# CRUVI.net
KiCad netlist of a schematic drawn in Altium Designer
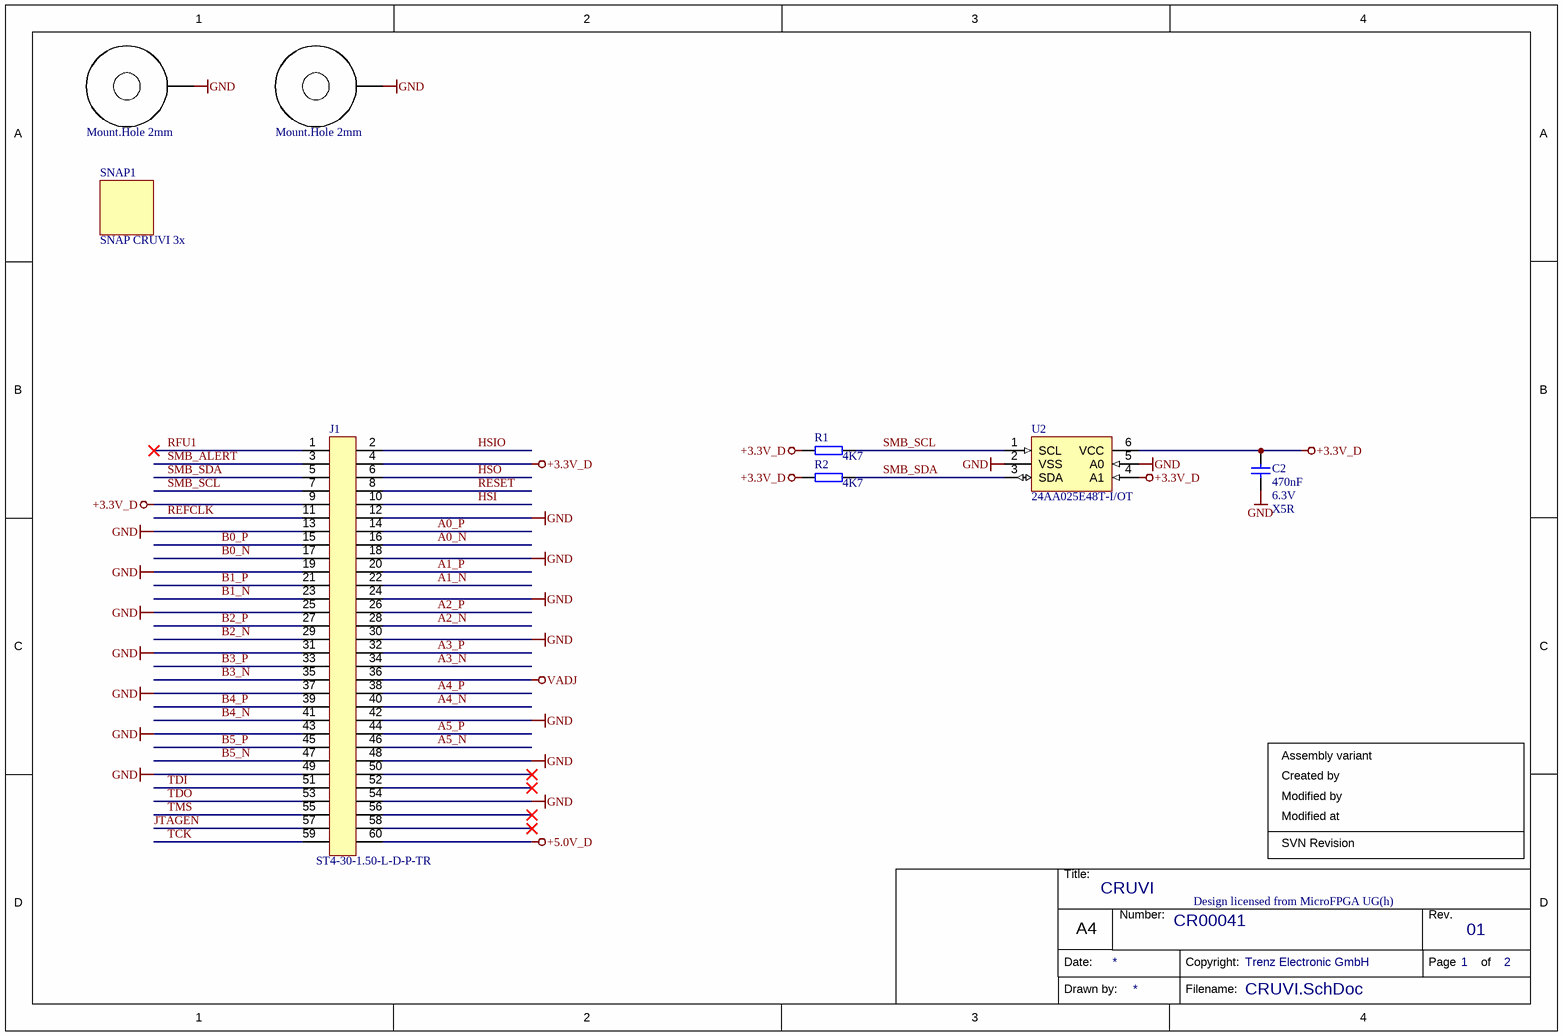
[diagram p0: CRUVI.SchDoc]

(export (version "E")
  (design (tool "Eeschema 10.0.6"))
  (components
    (comp (ref "C2")
      (value "470nF")
      (footprint "CAPC1005X55N")
      (description "KON 470nF 6,3V X5R SMD BF 1005 (0402)")
      (fields (field (name "VOLTAGE") "6.3V") (field (name "TECHNOLOGY") "X5R"))
      (libsource (lib "TE") (part "CAP-NP"))
    )
    (comp (ref "H1") (value "Mount.Hole 2mm") (footprint "MHole2_2mm") (libsource (lib "TE") (part "MHole")))
    (comp (ref "H2") (value "Mount.Hole 2mm") (footprint "MHole2_2mm") (libsource (lib "TE") (part "MHole")))
    (comp (ref "J1")
      (value "ST4-30-1.50-L-D-P-TR")
      (footprint "ST4-30-1_50-L-D")
      (libsource (lib "TE") (part "CON-60"))
    )
    (comp (ref "R1")
      (value "4K7")
      (footprint "RESC1005X40N")
      (description "WID SMD 4K7 1% 0,063W BF 1005 (0402)")
      (fields (field (name "TOLERANCE") "1%"))
      (libsource (lib "TE") (part "RES"))
    )
    (comp (ref "R2")
      (value "4K7")
      (footprint "RESC1005X40N")
      (description "WID SMD 4K7 1% 0,063W BF 1005 (0402)")
      (fields (field (name "TOLERANCE") "1%"))
      (libsource (lib "TE") (part "RES"))
    )
    (comp (ref "SNAP1")
      (value "SNAP CRUVI 3x")
      (footprint "CRUVI_3x_Snap")
      (description "SNAP for CRUVI 3x")
      (libsource (lib "TE") (part "DUMMY"))
    )
    (comp (ref "U2")
      (value "24AA025E48T-I/OT")
      (footprint "SOT95P280X145-6N")
      (libsource (lib "TE") (part "24AA025E48"))
    )
  )
  (nets
    (net (code "1") (name "+3.3V_D") (class "Default")
      (node (ref "C2") (pin "1") (pinfunction "1_1") (pintype "passive"))
      (node (ref "J1") (pin "4") (pinfunction "4_4") (pintype "passive"))
      (node (ref "J1") (pin "9") (pinfunction "9_9") (pintype "passive"))
      (node (ref "R1") (pin "1") (pinfunction "1_1") (pintype "passive"))
      (node (ref "R2") (pin "1") (pinfunction "1_1") (pintype "passive"))
      (node (ref "U2") (pin "4") (pinfunction "A1_4") (pintype "input"))
      (node (ref "U2") (pin "6") (pinfunction "VCC_6") (pintype "power_in"))
    )
    (net (code "2") (name "+5.0V_D") (class "Default")
      (node (ref "J1") (pin "60") (pinfunction "60_60") (pintype "passive"))
    )
    (net (code "3") (name "/A0_N") (class "Default")
      (node (ref "J1") (pin "16") (pinfunction "16_16") (pintype "passive"))
    )
    (net (code "4") (name "/A0_P") (class "Default")
      (node (ref "J1") (pin "14") (pinfunction "14_14") (pintype "passive"))
    )
    (net (code "5") (name "/A1_N") (class "Default")
      (node (ref "J1") (pin "22") (pinfunction "22_22") (pintype "passive"))
    )
    (net (code "6") (name "/A1_P") (class "Default")
      (node (ref "J1") (pin "20") (pinfunction "20_20") (pintype "passive"))
    )
    (net (code "7") (name "/A2_N") (class "Default")
      (node (ref "J1") (pin "28") (pinfunction "28_28") (pintype "passive"))
    )
    (net (code "8") (name "/A2_P") (class "Default")
      (node (ref "J1") (pin "26") (pinfunction "26_26") (pintype "passive"))
    )
    (net (code "9") (name "/A3_N") (class "Default")
      (node (ref "J1") (pin "34") (pinfunction "34_34") (pintype "passive"))
    )
    (net (code "10") (name "/A3_P") (class "Default")
      (node (ref "J1") (pin "32") (pinfunction "32_32") (pintype "passive"))
    )
    (net (code "11") (name "/A4_N") (class "Default")
      (node (ref "J1") (pin "40") (pinfunction "40_40") (pintype "passive"))
    )
    (net (code "12") (name "/A4_P") (class "Default")
      (node (ref "J1") (pin "38") (pinfunction "38_38") (pintype "passive"))
    )
    (net (code "13") (name "/A5_N") (class "Default")
      (node (ref "J1") (pin "46") (pinfunction "46_46") (pintype "passive"))
    )
    (net (code "14") (name "/A5_P") (class "Default")
      (node (ref "J1") (pin "44") (pinfunction "44_44") (pintype "passive"))
    )
    (net (code "15") (name "/B0_N") (class "Default")
      (node (ref "J1") (pin "17") (pinfunction "17_17") (pintype "passive"))
    )
    (net (code "16") (name "/B0_P") (class "Default")
      (node (ref "J1") (pin "15") (pinfunction "15_15") (pintype "passive"))
    )
    (net (code "17") (name "/B1_N") (class "Default")
      (node (ref "J1") (pin "23") (pinfunction "23_23") (pintype "passive"))
    )
    (net (code "18") (name "/B1_P") (class "Default")
      (node (ref "J1") (pin "21") (pinfunction "21_21") (pintype "passive"))
    )
    (net (code "19") (name "/B2_N") (class "Default")
      (node (ref "J1") (pin "29") (pinfunction "29_29") (pintype "passive"))
    )
    (net (code "20") (name "/B2_P") (class "Default")
      (node (ref "J1") (pin "27") (pinfunction "27_27") (pintype "passive"))
    )
    (net (code "21") (name "/B3_N") (class "Default")
      (node (ref "J1") (pin "35") (pinfunction "35_35") (pintype "passive"))
    )
    (net (code "22") (name "/B3_P") (class "Default")
      (node (ref "J1") (pin "33") (pinfunction "33_33") (pintype "passive"))
    )
    (net (code "23") (name "/B4_N") (class "Default")
      (node (ref "J1") (pin "41") (pinfunction "41_41") (pintype "passive"))
    )
    (net (code "24") (name "/B4_P") (class "Default")
      (node (ref "J1") (pin "39") (pinfunction "39_39") (pintype "passive"))
    )
    (net (code "25") (name "/B5_N") (class "Default")
      (node (ref "J1") (pin "47") (pinfunction "47_47") (pintype "passive"))
    )
    (net (code "26") (name "/B5_P") (class "Default")
      (node (ref "J1") (pin "45") (pinfunction "45_45") (pintype "passive"))
    )
    (net (code "27") (name "/HSI") (class "Default")
      (node (ref "J1") (pin "10") (pinfunction "10_10") (pintype "passive"))
    )
    (net (code "28") (name "/HSIO") (class "Default")
      (node (ref "J1") (pin "2") (pinfunction "2_2") (pintype "passive"))
    )
    (net (code "29") (name "/HSO") (class "Default")
      (node (ref "J1") (pin "6") (pinfunction "6_6") (pintype "passive"))
    )
    (net (code "30") (name "/JTAGEN") (class "Default")
      (node (ref "J1") (pin "57") (pinfunction "57_57") (pintype "passive"))
    )
    (net (code "31") (name "/REFCLK") (class "Default")
      (node (ref "J1") (pin "11") (pinfunction "11_11") (pintype "passive"))
    )
    (net (code "32") (name "/RESET") (class "Default")
      (node (ref "J1") (pin "8") (pinfunction "8_8") (pintype "passive"))
    )
    (net (code "33") (name "/RFU1") (class "Default")
      (node (ref "J1") (pin "1") (pinfunction "1_1") (pintype "passive+no_connect"))
    )
    (net (code "34") (name "/SMB_ALERT") (class "Default")
      (node (ref "J1") (pin "3") (pinfunction "3_3") (pintype "passive"))
    )
    (net (code "35") (name "/SMB_SCL") (class "Default")
      (node (ref "J1") (pin "7") (pinfunction "7_7") (pintype "passive"))
      (node (ref "R1") (pin "2") (pinfunction "2_2") (pintype "passive"))
      (node (ref "U2") (pin "1") (pinfunction "SCL_1") (pintype "input"))
    )
    (net (code "36") (name "/SMB_SDA") (class "Default")
      (node (ref "J1") (pin "5") (pinfunction "5_5") (pintype "passive"))
      (node (ref "R2") (pin "2") (pinfunction "2_2") (pintype "passive"))
      (node (ref "U2") (pin "3") (pinfunction "SDA_3") (pintype "bidirectional"))
    )
    (net (code "37") (name "/TCK") (class "Default")
      (node (ref "J1") (pin "59") (pinfunction "59_59") (pintype "passive"))
    )
    (net (code "38") (name "/TDI") (class "Default")
      (node (ref "J1") (pin "51") (pinfunction "51_51") (pintype "passive"))
    )
    (net (code "39") (name "/TDO") (class "Default")
      (node (ref "J1") (pin "53") (pinfunction "53_53") (pintype "passive"))
    )
    (net (code "40") (name "/TMS") (class "Default")
      (node (ref "J1") (pin "55") (pinfunction "55_55") (pintype "passive"))
    )
    (net (code "41") (name "GND") (class "Default")
      (node (ref "C2") (pin "2") (pinfunction "2_2") (pintype "passive"))
      (node (ref "H1") (pin "1") (pinfunction "1_1") (pintype "passive"))
      (node (ref "H2") (pin "1") (pinfunction "1_1") (pintype "passive"))
      (node (ref "J1") (pin "12") (pinfunction "12_12") (pintype "passive"))
      (node (ref "J1") (pin "13") (pinfunction "13_13") (pintype "passive"))
      (node (ref "J1") (pin "18") (pinfunction "18_18") (pintype "passive"))
      (node (ref "J1") (pin "19") (pinfunction "19_19") (pintype "passive"))
      (node (ref "J1") (pin "24") (pinfunction "24_24") (pintype "passive"))
      (node (ref "J1") (pin "25") (pinfunction "25_25") (pintype "passive"))
      (node (ref "J1") (pin "30") (pinfunction "30_30") (pintype "passive"))
      (node (ref "J1") (pin "31") (pinfunction "31_31") (pintype "passive"))
      (node (ref "J1") (pin "37") (pinfunction "37_37") (pintype "passive"))
      (node (ref "J1") (pin "42") (pinfunction "42_42") (pintype "passive"))
      (node (ref "J1") (pin "43") (pinfunction "43_43") (pintype "passive"))
      (node (ref "J1") (pin "48") (pinfunction "48_48") (pintype "passive"))
      (node (ref "J1") (pin "49") (pinfunction "49_49") (pintype "passive"))
      (node (ref "J1") (pin "54") (pinfunction "54_54") (pintype "passive"))
      (node (ref "U2") (pin "2") (pinfunction "VSS_2") (pintype "power_in"))
      (node (ref "U2") (pin "5") (pinfunction "A0_5") (pintype "input"))
    )
    (net (code "42") (name "VADJ") (class "Default")
      (node (ref "J1") (pin "36") (pinfunction "36_36") (pintype "passive"))
    )
    (net (code "43") (name "unconnected-(J1-Pad50)") (class "Default")
      (node (ref "J1") (pin "50") (pinfunction "50_50") (pintype "passive+no_connect"))
    )
    (net (code "44") (name "unconnected-(J1-Pad52)") (class "Default")
      (node (ref "J1") (pin "52") (pinfunction "52_52") (pintype "passive+no_connect"))
    )
    (net (code "45") (name "unconnected-(J1-Pad56)") (class "Default")
      (node (ref "J1") (pin "56") (pinfunction "56_56") (pintype "passive+no_connect"))
    )
    (net (code "46") (name "unconnected-(J1-Pad58)") (class "Default")
      (node (ref "J1") (pin "58") (pinfunction "58_58") (pintype "passive+no_connect"))
    )
  )
)
